# M960old.net
KiCad netlist of a schematic drawn in EAGLE
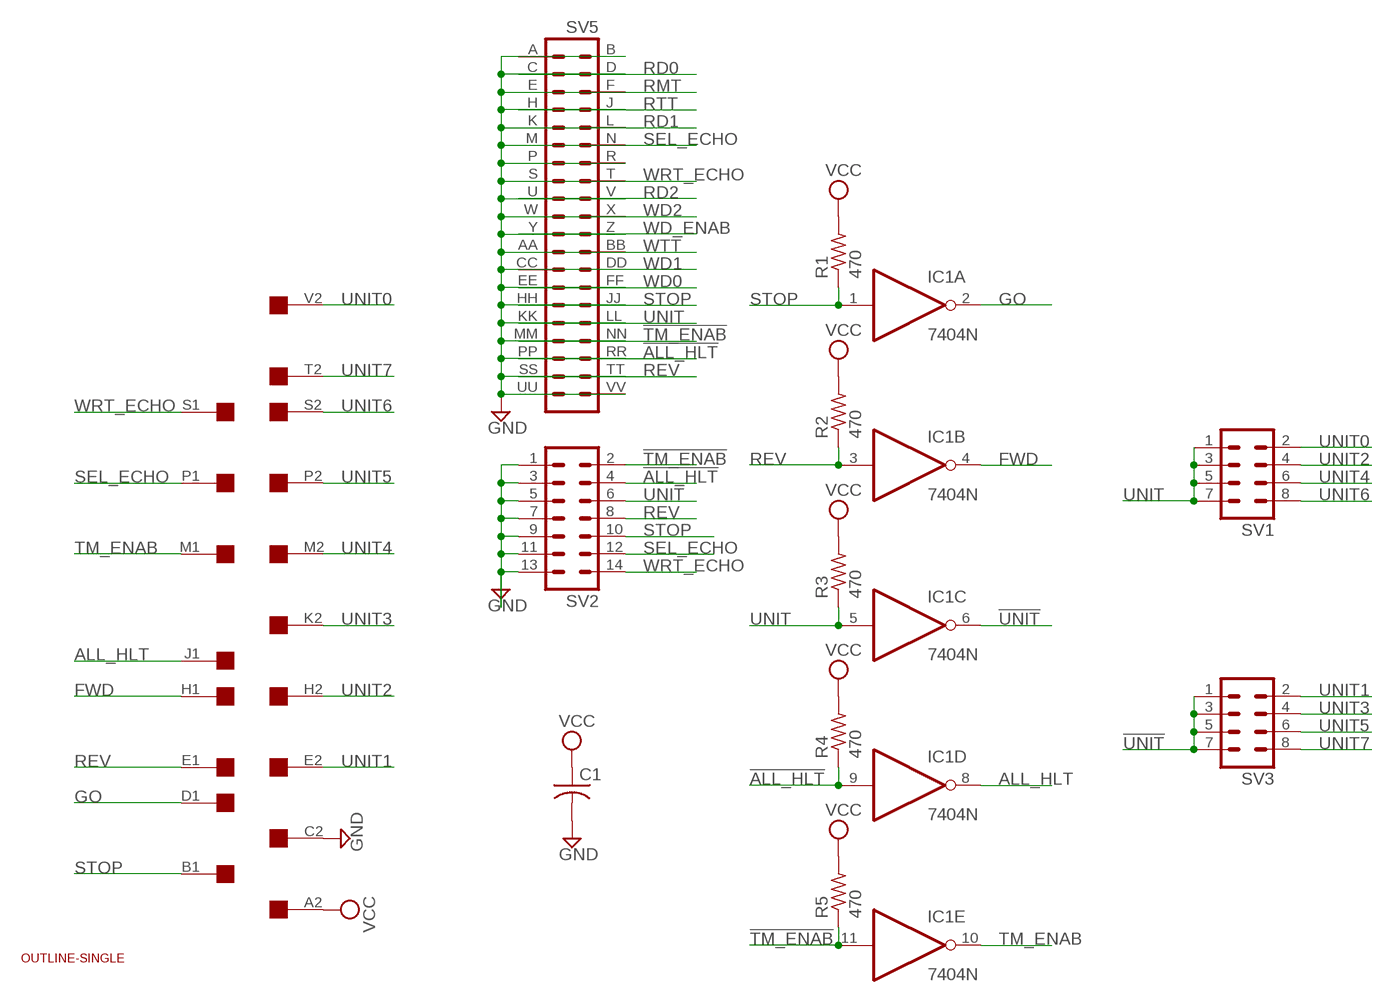
[diagram p0: schematic, sheet 1]

(export (version "E")
  (design (tool "Eeschema 10.0.6"))
  (components
    (comp (ref "C1")
      (value "C-US050-025X075")
      (footprint "eagle-import:C050-025X075")
      (libsource (lib "eagle-import") (part "C-US050-025X075"))
    )
    (comp (ref "IC1")
      (value "7404N")
      (footprint "eagle-import:DIL14")
      (libsource (lib "eagle-import") (part "7404N"))
    )
    (comp (ref "R1")
      (value "470")
      (footprint "eagle-import:0207_10")
      (libsource (lib "eagle-import") (part "R-US_0207/10"))
    )
    (comp (ref "R2")
      (value "470")
      (footprint "eagle-import:0207_10")
      (libsource (lib "eagle-import") (part "R-US_0207/10"))
    )
    (comp (ref "R3")
      (value "470")
      (footprint "eagle-import:0207_10")
      (libsource (lib "eagle-import") (part "R-US_0207/10"))
    )
    (comp (ref "R4")
      (value "470")
      (footprint "eagle-import:0207_10")
      (libsource (lib "eagle-import") (part "R-US_0207/10"))
    )
    (comp (ref "R5")
      (value "470")
      (footprint "eagle-import:0207_10")
      (libsource (lib "eagle-import") (part "R-US_0207/10"))
    )
    (comp (ref "SV1")
      (value "MA04-2")
      (footprint "eagle-import:MA04-2")
      (libsource (lib "eagle-import") (part "MA04-2"))
    )
    (comp (ref "SV2")
      (value "MA07-2")
      (footprint "eagle-import:MA07-2")
      (libsource (lib "eagle-import") (part "MA07-2"))
    )
    (comp (ref "SV3")
      (value "MA04-2")
      (footprint "eagle-import:MA04-2")
      (libsource (lib "eagle-import") (part "MA04-2"))
    )
    (comp (ref "SV5")
      (value "DEC40PINV")
      (footprint "eagle-import:DEC40PINV")
      (libsource (lib "eagle-import") (part "DEC40PINV"))
    )
    (comp (ref "U$1")
      (value "OUTLINE-SINGLE")
      (footprint "eagle-import:SINGLE")
      (libsource (lib "eagle-import") (part "OUTLINE-SINGLE"))
    )
    (comp (ref "U$2")
      (value "SINGLE")
      (footprint "eagle-import:EDGE-CON2")
      (libsource (lib "eagle-import") (part "SINGLE"))
    )
  )
  (nets
    (net (code "1") (name "/ALL_HLT") (class "Default")
      (node (ref "IC1") (pin "8") (pinfunction "O_8") (pintype "output"))
      (node (ref "U$2") (pin "J1") (pinfunction "1_J1") (pintype "bidirectional"))
    )
    (net (code "2") (name "/FWD") (class "Default")
      (node (ref "IC1") (pin "4") (pinfunction "O_4") (pintype "output"))
      (node (ref "U$2") (pin "H1") (pinfunction "1_H1") (pintype "bidirectional"))
    )
    (net (code "3") (name "/GO") (class "Default")
      (node (ref "IC1") (pin "2") (pinfunction "O_2") (pintype "output"))
      (node (ref "U$2") (pin "D1") (pinfunction "1_D1") (pintype "bidirectional"))
    )
    (net (code "4") (name "/RD0") (class "Default")
      (node (ref "SV5") (pin "C") (pinfunction "3_C") (pintype "bidirectional"))
    )
    (net (code "5") (name "/RD1") (class "Default")
      (node (ref "SV5") (pin "K") (pinfunction "9_K") (pintype "bidirectional"))
    )
    (net (code "6") (name "/RD2") (class "Default")
      (node (ref "SV5") (pin "U") (pinfunction "17_U") (pintype "bidirectional"))
    )
    (net (code "7") (name "/REV") (class "Default")
      (node (ref "IC1") (pin "3") (pinfunction "I_3") (pintype "input"))
      (node (ref "R2") (pin "1") (pinfunction "1_1") (pintype "passive"))
      (node (ref "SV2") (pin "8") (pinfunction "8_8") (pintype "passive"))
      (node (ref "SV5") (pin "SS") (pinfunction "37_SS") (pintype "bidirectional"))
      (node (ref "U$2") (pin "E1") (pinfunction "1_E1") (pintype "bidirectional"))
    )
    (net (code "8") (name "/RMT") (class "Default")
      (node (ref "SV5") (pin "E") (pinfunction "5_E") (pintype "bidirectional"))
    )
    (net (code "9") (name "/RTT") (class "Default")
      (node (ref "SV5") (pin "H") (pinfunction "7_H") (pintype "bidirectional"))
    )
    (net (code "10") (name "/SEL_ECHO") (class "Default")
      (node (ref "SV2") (pin "12") (pinfunction "12_12") (pintype "passive"))
      (node (ref "SV5") (pin "M") (pinfunction "11_M") (pintype "bidirectional"))
      (node (ref "U$2") (pin "P1") (pinfunction "1_P1") (pintype "bidirectional"))
    )
    (net (code "11") (name "/STOP") (class "Default")
      (node (ref "IC1") (pin "1") (pinfunction "I_1") (pintype "input"))
      (node (ref "R1") (pin "1") (pinfunction "1_1") (pintype "passive"))
      (node (ref "SV2") (pin "10") (pinfunction "10_10") (pintype "passive"))
      (node (ref "SV5") (pin "HH") (pinfunction "29_HH") (pintype "bidirectional"))
      (node (ref "U$2") (pin "B1") (pinfunction "1_B1") (pintype "bidirectional"))
    )
    (net (code "12") (name "/TM_ENAB") (class "Default")
      (node (ref "IC1") (pin "10") (pinfunction "O_10") (pintype "output"))
      (node (ref "U$2") (pin "M1") (pinfunction "1_M1") (pintype "bidirectional"))
    )
    (net (code "13") (name "/UNIT") (class "Default")
      (node (ref "IC1") (pin "5") (pinfunction "I_5") (pintype "input"))
      (node (ref "R3") (pin "1") (pinfunction "1_1") (pintype "passive"))
      (node (ref "SV1") (pin "1") (pinfunction "1_1") (pintype "passive"))
      (node (ref "SV1") (pin "3") (pinfunction "3_3") (pintype "passive"))
      (node (ref "SV1") (pin "5") (pinfunction "5_5") (pintype "passive"))
      (node (ref "SV1") (pin "7") (pinfunction "7_7") (pintype "passive"))
      (node (ref "SV2") (pin "6") (pinfunction "6_6") (pintype "passive"))
      (node (ref "SV5") (pin "KK") (pinfunction "31_KK") (pintype "bidirectional"))
    )
    (net (code "14") (name "/UNIT0") (class "Default")
      (node (ref "SV1") (pin "2") (pinfunction "2_2") (pintype "passive"))
      (node (ref "U$2") (pin "V2") (pinfunction "1_V2") (pintype "bidirectional"))
    )
    (net (code "15") (name "/UNIT1") (class "Default")
      (node (ref "SV3") (pin "2") (pinfunction "2_2") (pintype "passive"))
      (node (ref "U$2") (pin "E2") (pinfunction "1_E2") (pintype "bidirectional"))
    )
    (net (code "16") (name "/UNIT2") (class "Default")
      (node (ref "SV1") (pin "4") (pinfunction "4_4") (pintype "passive"))
      (node (ref "U$2") (pin "H2") (pinfunction "1_H2") (pintype "bidirectional"))
    )
    (net (code "17") (name "/UNIT3") (class "Default")
      (node (ref "SV3") (pin "4") (pinfunction "4_4") (pintype "passive"))
      (node (ref "U$2") (pin "K2") (pinfunction "1_K2") (pintype "bidirectional"))
    )
    (net (code "18") (name "/UNIT4") (class "Default")
      (node (ref "SV1") (pin "6") (pinfunction "6_6") (pintype "passive"))
      (node (ref "U$2") (pin "M2") (pinfunction "1_M2") (pintype "bidirectional"))
    )
    (net (code "19") (name "/UNIT5") (class "Default")
      (node (ref "SV3") (pin "6") (pinfunction "6_6") (pintype "passive"))
      (node (ref "U$2") (pin "P2") (pinfunction "1_P2") (pintype "bidirectional"))
    )
    (net (code "20") (name "/UNIT6") (class "Default")
      (node (ref "SV1") (pin "8") (pinfunction "8_8") (pintype "passive"))
      (node (ref "U$2") (pin "S2") (pinfunction "1_S2") (pintype "bidirectional"))
    )
    (net (code "21") (name "/UNIT7") (class "Default")
      (node (ref "SV3") (pin "8") (pinfunction "8_8") (pintype "passive"))
      (node (ref "U$2") (pin "T2") (pinfunction "1_T2") (pintype "bidirectional"))
    )
    (net (code "22") (name "/WD0") (class "Default")
      (node (ref "SV5") (pin "EE") (pinfunction "27_EE") (pintype "bidirectional"))
    )
    (net (code "23") (name "/WD1") (class "Default")
      (node (ref "SV5") (pin "CC") (pinfunction "25_CC") (pintype "bidirectional"))
    )
    (net (code "24") (name "/WD2") (class "Default")
      (node (ref "SV5") (pin "W") (pinfunction "19_W") (pintype "bidirectional"))
    )
    (net (code "25") (name "/WD_ENAB") (class "Default")
      (node (ref "SV5") (pin "Y") (pinfunction "21_Y") (pintype "bidirectional"))
    )
    (net (code "26") (name "/WRT_ECHO") (class "Default")
      (node (ref "SV2") (pin "14") (pinfunction "14_14") (pintype "passive"))
      (node (ref "SV5") (pin "S") (pinfunction "15_S") (pintype "bidirectional"))
      (node (ref "U$2") (pin "S1") (pinfunction "1_S1") (pintype "bidirectional"))
    )
    (net (code "27") (name "/WTT") (class "Default")
      (node (ref "SV5") (pin "AA") (pinfunction "23_AA") (pintype "bidirectional"))
    )
    (net (code "28") (name "/~{ALL_HLT}") (class "Default")
      (node (ref "IC1") (pin "9") (pinfunction "I_9") (pintype "input"))
      (node (ref "R4") (pin "1") (pinfunction "1_1") (pintype "passive"))
      (node (ref "SV2") (pin "4") (pinfunction "4_4") (pintype "passive"))
      (node (ref "SV5") (pin "PP") (pinfunction "35_PP") (pintype "bidirectional"))
    )
    (net (code "29") (name "/~{TM_ENAB}") (class "Default")
      (node (ref "IC1") (pin "11") (pinfunction "I_11") (pintype "input"))
      (node (ref "R5") (pin "1") (pinfunction "1_1") (pintype "passive"))
      (node (ref "SV2") (pin "2") (pinfunction "2_2") (pintype "passive"))
      (node (ref "SV5") (pin "MM") (pinfunction "33_MM") (pintype "bidirectional"))
    )
    (net (code "30") (name "/~{UNIT}") (class "Default")
      (node (ref "IC1") (pin "6") (pinfunction "O_6") (pintype "output"))
      (node (ref "SV3") (pin "1") (pinfunction "1_1") (pintype "passive"))
      (node (ref "SV3") (pin "3") (pinfunction "3_3") (pintype "passive"))
      (node (ref "SV3") (pin "5") (pinfunction "5_5") (pintype "passive"))
      (node (ref "SV3") (pin "7") (pinfunction "7_7") (pintype "passive"))
    )
    (net (code "31") (name "GND") (class "Default")
      (node (ref "C1") (pin "2") (pinfunction "2_2") (pintype "passive"))
      (node (ref "SV2") (pin "1") (pinfunction "1_1") (pintype "passive"))
      (node (ref "SV2") (pin "11") (pinfunction "11_11") (pintype "passive"))
      (node (ref "SV2") (pin "13") (pinfunction "13_13") (pintype "passive"))
      (node (ref "SV2") (pin "3") (pinfunction "3_3") (pintype "passive"))
      (node (ref "SV2") (pin "5") (pinfunction "5_5") (pintype "passive"))
      (node (ref "SV2") (pin "7") (pinfunction "7_7") (pintype "passive"))
      (node (ref "SV2") (pin "9") (pinfunction "9_9") (pintype "passive"))
      (node (ref "SV5") (pin "B") (pinfunction "2_B") (pintype "bidirectional"))
      (node (ref "SV5") (pin "BB") (pinfunction "24_BB") (pintype "bidirectional"))
      (node (ref "SV5") (pin "D") (pinfunction "4_D") (pintype "bidirectional"))
      (node (ref "SV5") (pin "DD") (pinfunction "26_DD") (pintype "bidirectional"))
      (node (ref "SV5") (pin "F") (pinfunction "6_F") (pintype "bidirectional"))
      (node (ref "SV5") (pin "FF") (pinfunction "28_FF") (pintype "bidirectional"))
      (node (ref "SV5") (pin "J") (pinfunction "8_J") (pintype "bidirectional"))
      (node (ref "SV5") (pin "JJ") (pinfunction "30_JJ") (pintype "bidirectional"))
      (node (ref "SV5") (pin "L") (pinfunction "10_L") (pintype "bidirectional"))
      (node (ref "SV5") (pin "LL") (pinfunction "32_LL") (pintype "bidirectional"))
      (node (ref "SV5") (pin "N") (pinfunction "12_N") (pintype "bidirectional"))
      (node (ref "SV5") (pin "NN") (pinfunction "34_NN") (pintype "bidirectional"))
      (node (ref "SV5") (pin "R") (pinfunction "14_R") (pintype "bidirectional"))
      (node (ref "SV5") (pin "RR") (pinfunction "36_RR") (pintype "bidirectional"))
      (node (ref "SV5") (pin "T") (pinfunction "16_T") (pintype "bidirectional"))
      (node (ref "SV5") (pin "TT") (pinfunction "38_TT") (pintype "bidirectional"))
      (node (ref "SV5") (pin "V") (pinfunction "18_V") (pintype "bidirectional"))
      (node (ref "SV5") (pin "VV") (pinfunction "40_VV") (pintype "bidirectional"))
      (node (ref "SV5") (pin "X") (pinfunction "20_X") (pintype "bidirectional"))
      (node (ref "SV5") (pin "Z") (pinfunction "22_Z") (pintype "bidirectional"))
      (node (ref "U$2") (pin "C2") (pinfunction "1_C2") (pintype "bidirectional"))
    )
    (net (code "32") (name "VCC") (class "Default")
      (node (ref "C1") (pin "1") (pinfunction "1_1") (pintype "passive"))
      (node (ref "R1") (pin "2") (pinfunction "2_2") (pintype "passive"))
      (node (ref "R2") (pin "2") (pinfunction "2_2") (pintype "passive"))
      (node (ref "R3") (pin "2") (pinfunction "2_2") (pintype "passive"))
      (node (ref "R4") (pin "2") (pinfunction "2_2") (pintype "passive"))
      (node (ref "R5") (pin "2") (pinfunction "2_2") (pintype "passive"))
      (node (ref "U$2") (pin "A2") (pinfunction "1_A2") (pintype "bidirectional"))
    )
    (net (code "33") (name "unconnected-(SV5-1-PadA)") (class "Default")
      (node (ref "SV5") (pin "A") (pinfunction "1_A") (pintype "bidirectional"))
    )
    (net (code "34") (name "unconnected-(SV5-13-PadP)") (class "Default")
      (node (ref "SV5") (pin "P") (pinfunction "13_P") (pintype "bidirectional"))
    )
    (net (code "35") (name "unconnected-(SV5-39-PadUU)") (class "Default")
      (node (ref "SV5") (pin "UU") (pinfunction "39_UU") (pintype "bidirectional"))
    )
  )
)
